# ADL5511.net
KiCad netlist of a schematic drawn in Altium Designer
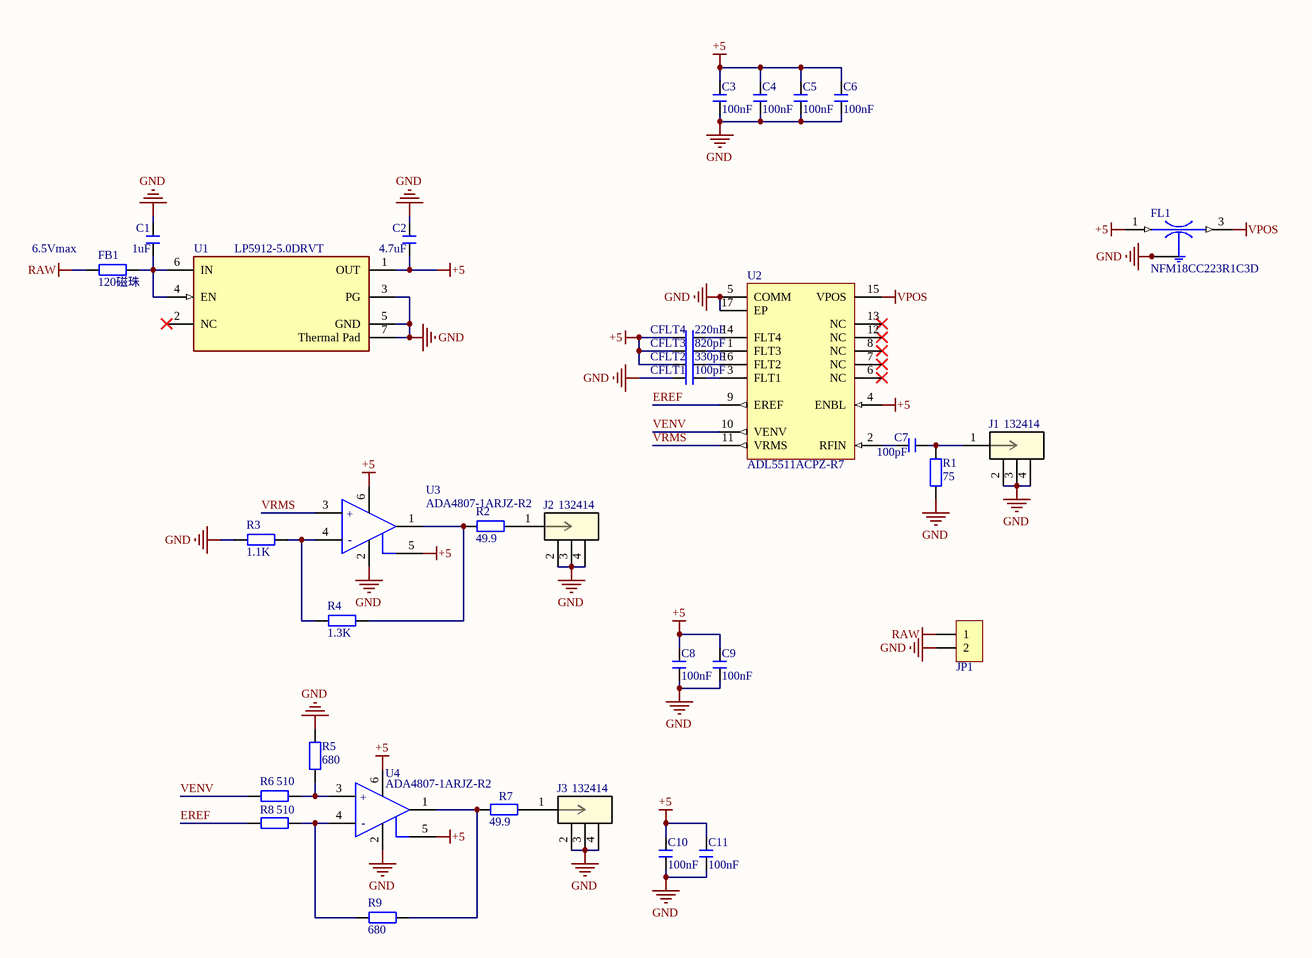
[diagram p0: ADL5511.SchDoc]

(export (version "E")
  (design (tool "Eeschema 10.0.6"))
  (components
    (comp (ref "C1")
      (value "1uF")
      (footprint "C 0603_L")
      (description "贴片电容")
      (libsource (lib "01 - 电容-电阻-电感") (part "C"))
    )
    (comp (ref "C2")
      (value "4.7uF")
      (footprint "C 0603_L")
      (description "贴片电容")
      (libsource (lib "01 - 电容-电阻-电感") (part "C"))
    )
    (comp (ref "C3")
      (value "100nF")
      (footprint "C 0402_L")
      (description "贴片电容")
      (libsource (lib "01 - 电容-电阻-电感") (part "C"))
    )
    (comp (ref "C4")
      (value "100nF")
      (footprint "C 0402_L")
      (description "贴片电容")
      (libsource (lib "01 - 电容-电阻-电感") (part "C"))
    )
    (comp (ref "C5")
      (value "100nF")
      (footprint "C 0402_L")
      (description "贴片电容")
      (libsource (lib "01 - 电容-电阻-电感") (part "C"))
    )
    (comp (ref "C6")
      (value "100nF")
      (footprint "C 0402_L")
      (description "贴片电容")
      (libsource (lib "01 - 电容-电阻-电感") (part "C"))
    )
    (comp (ref "C7")
      (value "100pF")
      (footprint "C 0402_L")
      (description "贴片电容")
      (libsource (lib "01 - 电容-电阻-电感") (part "C"))
    )
    (comp (ref "C8")
      (value "100nF")
      (footprint "C 0402_L")
      (description "贴片电容")
      (libsource (lib "01 - 电容-电阻-电感") (part "C"))
    )
    (comp (ref "C9")
      (value "100nF")
      (footprint "C 0402_L")
      (description "贴片电容")
      (libsource (lib "01 - 电容-电阻-电感") (part "C"))
    )
    (comp (ref "C10")
      (value "100nF")
      (footprint "C 0402_L")
      (description "贴片电容")
      (libsource (lib "01 - 电容-电阻-电感") (part "C"))
    )
    (comp (ref "C11")
      (value "100nF")
      (footprint "C 0402_L")
      (description "贴片电容")
      (libsource (lib "01 - 电容-电阻-电感") (part "C"))
    )
    (comp (ref "CFLT1")
      (value "100pF")
      (footprint "C 0402_L")
      (description "贴片电容")
      (libsource (lib "01 - 电容-电阻-电感") (part "C"))
    )
    (comp (ref "CFLT2")
      (value "330pF")
      (footprint "C 0402_L")
      (description "贴片电容")
      (libsource (lib "01 - 电容-电阻-电感") (part "C"))
    )
    (comp (ref "CFLT3")
      (value "820pF")
      (footprint "C 0402_L")
      (description "贴片电容")
      (libsource (lib "01 - 电容-电阻-电感") (part "C"))
    )
    (comp (ref "CFLT4")
      (value "220nF")
      (footprint "C 0402_L")
      (description "贴片电容")
      (libsource (lib "01 - 电容-电阻-电感") (part "C"))
    )
    (comp (ref "FB1")
      (value "120磁珠")
      (footprint "R 0603_L")
      (description "贴片电阻")
      (libsource (lib "01 - 电容-电阻-电感") (part "R"))
    )
    (comp (ref "FL1")
      (value "NFM18CC223R1C3D")
      (footprint "FIL_NFM18CC223R1C3D")
      (description "SMD Capacitor with Capacitance: 22000pF Tol. 20%. Rated Voltage: 16Vdc")
      (fields (field (name "MF") "Murata"))
      (libsource (lib "NFM18CC223R1C3D") (part "NFM18CC223R1C3D"))
    )
    (comp (ref "J1")
      (value "132414")
      (footprint "CONN_132414_AMP")
      (description "No Description Available")
      (fields (field (name "COPYRIGHT") "Copyright (C) 2022 Ultra Librarian. All rights reserved."))
      (libsource (lib "细针大偏脚SMA(用这个)") (part "132414"))
    )
    (comp (ref "J2")
      (value "132414")
      (footprint "CONN_132414_AMP")
      (description "No Description Available")
      (fields (field (name "COPYRIGHT") "Copyright (C) 2022 Ultra Librarian. All rights reserved."))
      (libsource (lib "细针大偏脚SMA(用这个)") (part "132414"))
    )
    (comp (ref "J3")
      (value "132414")
      (footprint "CONN_132414_AMP")
      (description "No Description Available")
      (fields (field (name "COPYRIGHT") "Copyright (C) 2022 Ultra Librarian. All rights reserved."))
      (libsource (lib "细针大偏脚SMA(用这个)") (part "132414"))
    )
    (comp (ref "JP1")
      (value "HDR-1X2")
      (footprint "KF2510-LI-2P")
      (description "2P接插件")
      (libsource (lib "18 - 接插件-脚距2.54mm (100mil) ") (part "Header 2"))
    )
    (comp (ref "R1")
      (value "75")
      (footprint "R 0402_L")
      (description "贴片电阻")
      (libsource (lib "01 - 电容-电阻-电感") (part "R"))
    )
    (comp (ref "R2")
      (value "49.9")
      (footprint "R 0402_L")
      (description "贴片电阻")
      (libsource (lib "01 - 电容-电阻-电感") (part "R"))
    )
    (comp (ref "R3")
      (value "1.1K")
      (footprint "R 0402_L")
      (description "贴片电阻")
      (libsource (lib "01 - 电容-电阻-电感") (part "R"))
    )
    (comp (ref "R4")
      (value "1.3K")
      (footprint "R 0402_L")
      (description "贴片电阻")
      (libsource (lib "01 - 电容-电阻-电感") (part "R"))
    )
    (comp (ref "R5")
      (value "680")
      (footprint "R 0402_L")
      (description "贴片电阻")
      (libsource (lib "01 - 电容-电阻-电感") (part "R"))
    )
    (comp (ref "R6")
      (value "510")
      (footprint "R 0402_L")
      (description "贴片电阻")
      (libsource (lib "01 - 电容-电阻-电感") (part "R"))
    )
    (comp (ref "R7")
      (value "49.9")
      (footprint "R 0402_L")
      (description "贴片电阻")
      (libsource (lib "01 - 电容-电阻-电感") (part "R"))
    )
    (comp (ref "R8")
      (value "510")
      (footprint "R 0402_L")
      (description "贴片电阻")
      (libsource (lib "01 - 电容-电阻-电感") (part "R"))
    )
    (comp (ref "R9")
      (value "680")
      (footprint "R 0402_L")
      (description "贴片电阻")
      (libsource (lib "01 - 电容-电阻-电感") (part "R"))
    )
    (comp (ref "U1")
      (value "LP5912-5.0DRVT")
      (footprint "FP-DRV0006A-IPC_C")
      (description "IC REG LINEAR 5.0V 500MA 6SON")
      (libsource (lib "Altium Content Vault") (part "2f44a6c2e9bad9ae6b461b33d08ca99"))
    )
    (comp (ref "U2")
      (value "ADL5511ACPZ-R7")
      (footprint "ADI-CP-16-22_N")
      (description "DC to 6 GHz Envelope and TruPwr RMS Detector, CP-16-22, Pb-Free, 54 Tube")
      (libsource (lib "ADL5511") (part "CMP-0284-00041-1"))
    )
    (comp (ref "U3")
      (value "ADA4807-1ARJZ-R2")
      (footprint "FP-RJ-6-IPC_C")
      (description "IC OPAMP VFB 1 CIRCUIT SOT23-6")
      (libsource (lib "Altium Content Vault") (part "0cc169e61f44c0172c2773b4ba3b2c6"))
    )
    (comp (ref "U4")
      (value "ADA4807-1ARJZ-R2")
      (footprint "FP-RJ-6-IPC_C")
      (description "IC OPAMP VFB 1 CIRCUIT SOT23-6")
      (libsource (lib "Altium Content Vault") (part "0cc169e61f44c0172c2773b4ba3b2c6"))
    )
  )
  (nets
    (net (code "1") (name "+5") (class "Default")
      (node (ref "C10") (pin "2") (pinfunction "2_2") (pintype "passive"))
      (node (ref "C11") (pin "2") (pinfunction "2_2") (pintype "passive"))
      (node (ref "C2") (pin "1") (pinfunction "1_1") (pintype "passive"))
      (node (ref "C3") (pin "2") (pinfunction "2_2") (pintype "passive"))
      (node (ref "C4") (pin "2") (pinfunction "2_2") (pintype "passive"))
      (node (ref "C5") (pin "2") (pinfunction "2_2") (pintype "passive"))
      (node (ref "C6") (pin "2") (pinfunction "2_2") (pintype "passive"))
      (node (ref "C8") (pin "2") (pinfunction "2_2") (pintype "passive"))
      (node (ref "C9") (pin "2") (pinfunction "2_2") (pintype "passive"))
      (node (ref "CFLT2") (pin "1") (pinfunction "1_1") (pintype "passive"))
      (node (ref "CFLT3") (pin "1") (pinfunction "1_1") (pintype "passive"))
      (node (ref "CFLT4") (pin "1") (pinfunction "1_1") (pintype "passive"))
      (node (ref "FL1") (pin "1") (pinfunction "IN_1") (pintype "input"))
      (node (ref "U1") (pin "1") (pinfunction "OUT_1") (pintype "power_in"))
      (node (ref "U2") (pin "4") (pinfunction "ENBL_4") (pintype "input"))
      (node (ref "U3") (pin "5") (pinfunction "~{DISABLE}_5") (pintype "passive"))
      (node (ref "U3") (pin "6") (pinfunction "+VS_6") (pintype "power_in"))
      (node (ref "U4") (pin "5") (pinfunction "~{DISABLE}_5") (pintype "passive"))
      (node (ref "U4") (pin "6") (pinfunction "+VS_6") (pintype "power_in"))
    )
    (net (code "2") (name "/EREF") (class "Default")
      (node (ref "R8") (pin "1") (pinfunction "1_1") (pintype "passive"))
      (node (ref "U2") (pin "9") (pinfunction "EREF_9") (pintype "output"))
    )
    (net (code "3") (name "/VENV") (class "Default")
      (node (ref "R6") (pin "1") (pinfunction "1_1") (pintype "passive"))
      (node (ref "U2") (pin "10") (pinfunction "VENV_10") (pintype "output"))
    )
    (net (code "4") (name "/VRMS") (class "Default")
      (node (ref "U2") (pin "11") (pinfunction "VRMS_11") (pintype "output"))
      (node (ref "U3") (pin "3") (pinfunction "+IN_3") (pintype "tri_state"))
    )
    (net (code "5") (name "GND") (class "Default")
      (node (ref "C1") (pin "2") (pinfunction "2_2") (pintype "passive"))
      (node (ref "C10") (pin "1") (pinfunction "1_1") (pintype "passive"))
      (node (ref "C11") (pin "1") (pinfunction "1_1") (pintype "passive"))
      (node (ref "C2") (pin "2") (pinfunction "2_2") (pintype "passive"))
      (node (ref "C3") (pin "1") (pinfunction "1_1") (pintype "passive"))
      (node (ref "C4") (pin "1") (pinfunction "1_1") (pintype "passive"))
      (node (ref "C5") (pin "1") (pinfunction "1_1") (pintype "passive"))
      (node (ref "C6") (pin "1") (pinfunction "1_1") (pintype "passive"))
      (node (ref "C8") (pin "1") (pinfunction "1_1") (pintype "passive"))
      (node (ref "C9") (pin "1") (pinfunction "1_1") (pintype "passive"))
      (node (ref "CFLT1") (pin "1") (pinfunction "1_1") (pintype "passive"))
      (node (ref "FL1") (pin "2") (pinfunction "GND_2") (pintype "power_in"))
      (node (ref "FL1") (pin "2_1") (pinfunction "GND_2_1") (pintype "power_in"))
      (node (ref "J1") (pin "2") (pinfunction "2_2") (pintype "passive"))
      (node (ref "J1") (pin "3") (pinfunction "3_3") (pintype "passive"))
      (node (ref "J1") (pin "4") (pinfunction "4_4") (pintype "passive"))
      (node (ref "J2") (pin "2") (pinfunction "2_2") (pintype "passive"))
      (node (ref "J2") (pin "3") (pinfunction "3_3") (pintype "passive"))
      (node (ref "J2") (pin "4") (pinfunction "4_4") (pintype "passive"))
      (node (ref "J3") (pin "2") (pinfunction "2_2") (pintype "passive"))
      (node (ref "J3") (pin "3") (pinfunction "3_3") (pintype "passive"))
      (node (ref "J3") (pin "4") (pinfunction "4_4") (pintype "passive"))
      (node (ref "JP1") (pin "2") (pinfunction "2_2") (pintype "passive"))
      (node (ref "R1") (pin "1") (pinfunction "1_1") (pintype "passive"))
      (node (ref "R3") (pin "1") (pinfunction "1_1") (pintype "passive"))
      (node (ref "R5") (pin "1") (pinfunction "1_1") (pintype "passive"))
      (node (ref "U1") (pin "3") (pinfunction "PG_3") (pintype "open_collector"))
      (node (ref "U1") (pin "5") (pinfunction "GND_5") (pintype "power_in"))
      (node (ref "U1") (pin "7") (pinfunction "Thermal_Pad_7") (pintype "power_in"))
      (node (ref "U2") (pin "17") (pinfunction "EP_17") (pintype "power_in"))
      (node (ref "U2") (pin "5") (pinfunction "COMM_5") (pintype "power_in"))
      (node (ref "U3") (pin "2") (pinfunction "-VS_2") (pintype "power_in"))
      (node (ref "U4") (pin "2") (pinfunction "-VS_2") (pintype "power_in"))
    )
    (net (code "6") (name "Net-(C7-Pad2)") (class "Default")
      (node (ref "C7") (pin "2") (pinfunction "2_2") (pintype "passive"))
      (node (ref "J1") (pin "1") (pinfunction "1_1") (pintype "passive"))
      (node (ref "R1") (pin "2") (pinfunction "2_2") (pintype "passive"))
    )
    (net (code "7") (name "Net-(J2-Pad1)") (class "Default")
      (node (ref "J2") (pin "1") (pinfunction "1_1") (pintype "passive"))
      (node (ref "R2") (pin "2") (pinfunction "2_2") (pintype "passive"))
    )
    (net (code "8") (name "Net-(J3-Pad1)") (class "Default")
      (node (ref "J3") (pin "1") (pinfunction "1_1") (pintype "passive"))
      (node (ref "R7") (pin "2") (pinfunction "2_2") (pintype "passive"))
    )
    (net (code "9") (name "Net-(U1-EN)") (class "Default")
      (node (ref "C1") (pin "1") (pinfunction "1_1") (pintype "passive"))
      (node (ref "FB1") (pin "2") (pinfunction "2_2") (pintype "passive"))
      (node (ref "U1") (pin "4") (pinfunction "EN_4") (pintype "input"))
      (node (ref "U1") (pin "6") (pinfunction "IN_6") (pintype "power_in"))
    )
    (net (code "10") (name "Net-(U2-FLT1)") (class "Default")
      (node (ref "CFLT1") (pin "2") (pinfunction "2_2") (pintype "passive"))
      (node (ref "U2") (pin "3") (pinfunction "FLT1_3") (pintype "passive"))
    )
    (net (code "11") (name "Net-(U2-FLT2)") (class "Default")
      (node (ref "CFLT2") (pin "2") (pinfunction "2_2") (pintype "passive"))
      (node (ref "U2") (pin "16") (pinfunction "FLT2_16") (pintype "passive"))
    )
    (net (code "12") (name "Net-(U2-FLT3)") (class "Default")
      (node (ref "CFLT3") (pin "2") (pinfunction "2_2") (pintype "passive"))
      (node (ref "U2") (pin "1") (pinfunction "FLT3_1") (pintype "passive"))
    )
    (net (code "13") (name "Net-(U2-FLT4)") (class "Default")
      (node (ref "CFLT4") (pin "2") (pinfunction "2_2") (pintype "passive"))
      (node (ref "U2") (pin "14") (pinfunction "FLT4_14") (pintype "passive"))
    )
    (net (code "14") (name "Net-(U2-RFIN)") (class "Default")
      (node (ref "C7") (pin "1") (pinfunction "1_1") (pintype "passive"))
      (node (ref "U2") (pin "2") (pinfunction "RFIN_2") (pintype "input"))
    )
    (net (code "15") (name "Net-(U3--IN)") (class "Default")
      (node (ref "R3") (pin "2") (pinfunction "2_2") (pintype "passive"))
      (node (ref "R4") (pin "1") (pinfunction "1_1") (pintype "passive"))
      (node (ref "U3") (pin "4") (pinfunction "-IN_4") (pintype "tri_state"))
    )
    (net (code "16") (name "Net-(U3-VOUT)") (class "Default")
      (node (ref "R2") (pin "1") (pinfunction "1_1") (pintype "passive"))
      (node (ref "R4") (pin "2") (pinfunction "2_2") (pintype "passive"))
      (node (ref "U3") (pin "1") (pinfunction "VOUT_1") (pintype "passive"))
    )
    (net (code "17") (name "Net-(U4-+IN)") (class "Default")
      (node (ref "R5") (pin "2") (pinfunction "2_2") (pintype "passive"))
      (node (ref "R6") (pin "2") (pinfunction "2_2") (pintype "passive"))
      (node (ref "U4") (pin "3") (pinfunction "+IN_3") (pintype "tri_state"))
    )
    (net (code "18") (name "Net-(U4--IN)") (class "Default")
      (node (ref "R8") (pin "2") (pinfunction "2_2") (pintype "passive"))
      (node (ref "R9") (pin "1") (pinfunction "1_1") (pintype "passive"))
      (node (ref "U4") (pin "4") (pinfunction "-IN_4") (pintype "tri_state"))
    )
    (net (code "19") (name "Net-(U4-VOUT)") (class "Default")
      (node (ref "R7") (pin "1") (pinfunction "1_1") (pintype "passive"))
      (node (ref "R9") (pin "2") (pinfunction "2_2") (pintype "passive"))
      (node (ref "U4") (pin "1") (pinfunction "VOUT_1") (pintype "passive"))
    )
    (net (code "20") (name "RAW") (class "Default")
      (node (ref "FB1") (pin "1") (pinfunction "1_1") (pintype "passive"))
      (node (ref "JP1") (pin "1") (pinfunction "1_1") (pintype "passive"))
    )
    (net (code "21") (name "VPOS") (class "Default")
      (node (ref "FL1") (pin "3") (pinfunction "OUT_3") (pintype "output"))
      (node (ref "U2") (pin "15") (pinfunction "VPOS_15") (pintype "power_in"))
    )
    (net (code "22") (name "unconnected-(U1-NC-Pad2)") (class "Default")
      (node (ref "U1") (pin "2") (pinfunction "NC_2") (pintype "passive+no_connect"))
    )
    (net (code "23") (name "unconnected-(U2-NC-Pad6)") (class "Default")
      (node (ref "U2") (pin "6") (pinfunction "NC_6") (pintype "passive+no_connect"))
    )
    (net (code "24") (name "unconnected-(U2-NC-Pad7)") (class "Default")
      (node (ref "U2") (pin "7") (pinfunction "NC_7") (pintype "passive+no_connect"))
    )
    (net (code "25") (name "unconnected-(U2-NC-Pad8)") (class "Default")
      (node (ref "U2") (pin "8") (pinfunction "NC_8") (pintype "passive+no_connect"))
    )
    (net (code "26") (name "unconnected-(U2-NC-Pad12)") (class "Default")
      (node (ref "U2") (pin "12") (pinfunction "NC_12") (pintype "passive+no_connect"))
    )
    (net (code "27") (name "unconnected-(U2-NC-Pad13)") (class "Default")
      (node (ref "U2") (pin "13") (pinfunction "NC_13") (pintype "passive+no_connect"))
    )
  )
)
